# SRIC_Peripherals.net
KiCad netlist of a schematic drawn in Altium Designer
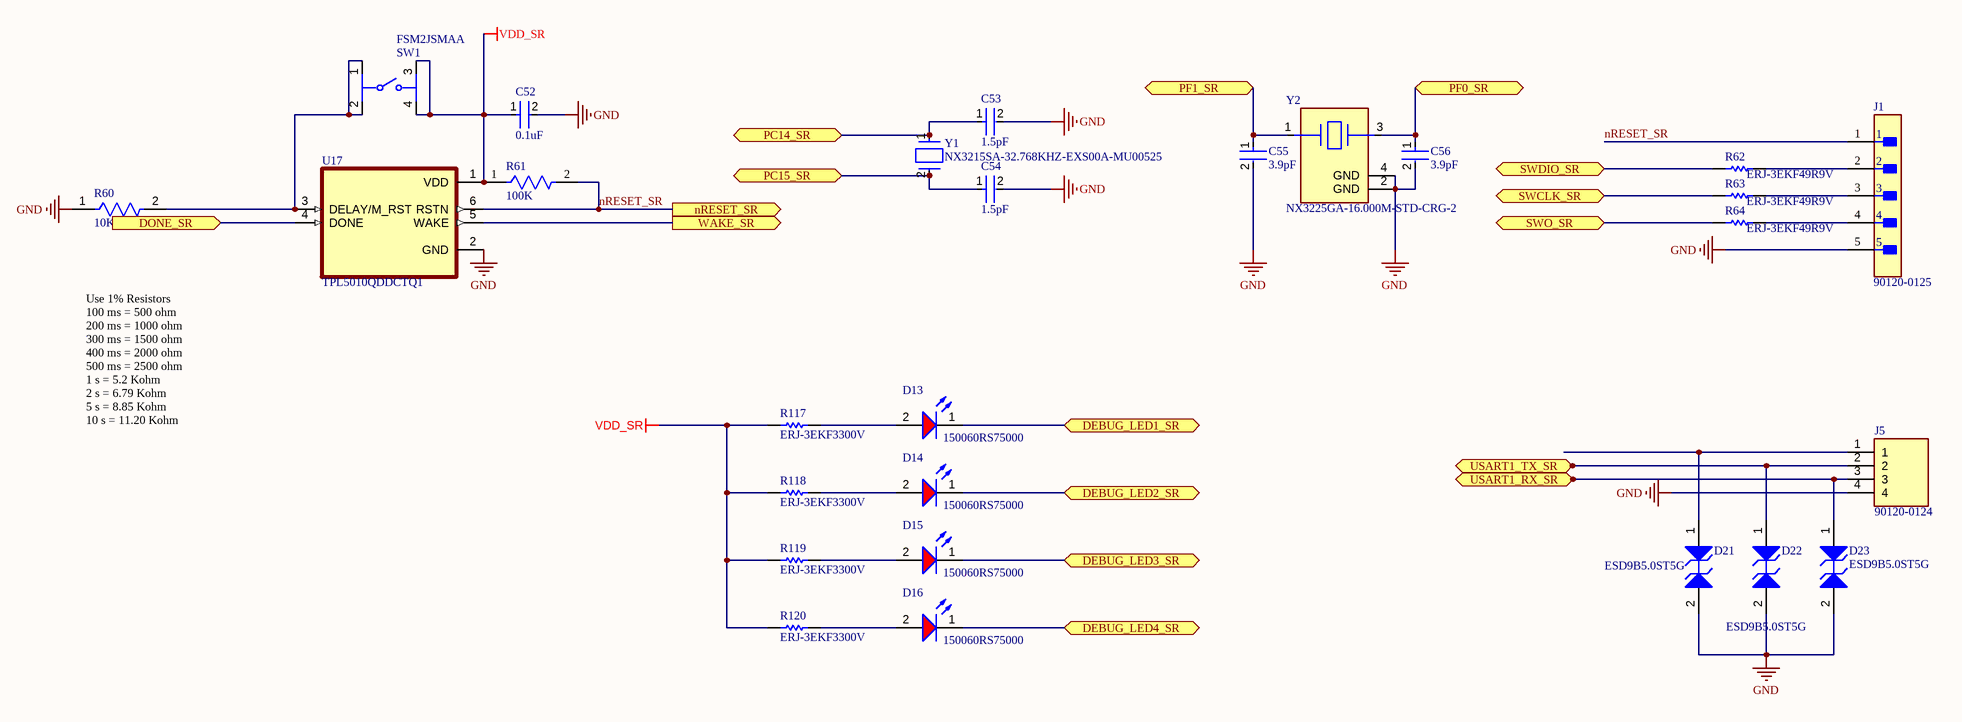
[diagram p0: SRIC_Peripherals.SchDoc]

(export (version "E")
  (design (tool "Eeschema 10.0.6"))
  (components
    (comp (ref "C52")
      (value "0.1uF")
      (footprint "FP-C0603C-CF-MFG")
      (description "CAP CER 0.1UF 50V X7R 0603")
      (fields (field (name "TOLERANCE") "0.1") (field (name "MANUFACTURER") "KEMET"))
      (libsource (lib "Altium Content Vault") (part "b4654b650e69147ec39a6b967a45e02"))
    )
    (comp (ref "C53")
      (value "1.5pF")
      (footprint "FP-C0603C-CF-MFG")
      (description "CAP CER 1.5PF 100V NP0 0603")
      (fields
        (field (name "MANUFACTURER PART NUMBER") "C0603C159C1GACTU")
        (field (name "TOLERANCE") "0.25 pF")
      )
      (libsource (lib "Altium Content Vault") (part "b4654b650e69147ec39a6b967a45e02"))
    )
    (comp (ref "C54")
      (value "1.5pF")
      (footprint "FP-C0603C-CF-MFG")
      (description "CAP CER 1.5PF 100V NP0 0603")
      (fields
        (field (name "MANUFACTURER PART NUMBER") "C0603C159C1GACTU")
        (field (name "TOLERANCE") "0.25 pF")
      )
      (libsource (lib "Altium Content Vault") (part "b4654b650e69147ec39a6b967a45e02"))
    )
    (comp (ref "C55")
      (value "3.9pF")
      (footprint "FP-CBR06C-MFG")
      (description "CAP CER 3.9PF 250V C0G/NP0 0603")
      (fields
        (field (name "OCTOPART") "https://octopart.com/cbr06c399cagac-kemet-20446767")
        (field (name "MANUFACTURER PART NUMBER") "CBR06C399CAGAC")
      )
      (libsource (lib "Altium Content Vault") (part "11868f565c42a9108669ba33697ecf6"))
    )
    (comp (ref "C56")
      (value "3.9pF")
      (footprint "FP-CBR06C-MFG")
      (description "CAP CER 3.9PF 250V C0G/NP0 0603")
      (fields
        (field (name "OCTOPART") "https://octopart.com/cbr06c399cagac-kemet-20446767")
        (field (name "MANUFACTURER PART NUMBER") "CBR06C399CAGAC")
      )
      (libsource (lib "Altium Content Vault") (part "11868f565c42a9108669ba33697ecf6"))
    )
    (comp (ref "D13")
      (value "150060RS75000")
      (footprint "WL-SMCW_0603_150060xx75000")
      (description "LED Low-Power Uni-Color Red 630nm 2V 2-Pin Chip 0603(1608Metric) T/R")
      (libsource (lib "Altium Content Vault") (part "LED_Red_2A-1K"))
    )
    (comp (ref "D14")
      (value "150060RS75000")
      (footprint "WL-SMCW_0603_150060xx75000")
      (description "LED Low-Power Uni-Color Red 630nm 2V 2-Pin Chip 0603(1608Metric) T/R")
      (libsource (lib "Altium Content Vault") (part "LED_Red_2A-1K"))
    )
    (comp (ref "D15")
      (value "150060RS75000")
      (footprint "WL-SMCW_0603_150060xx75000")
      (description "LED Low-Power Uni-Color Red 630nm 2V 2-Pin Chip 0603(1608Metric) T/R")
      (libsource (lib "Altium Content Vault") (part "LED_Red_2A-1K"))
    )
    (comp (ref "D16")
      (value "150060RS75000")
      (footprint "WL-SMCW_0603_150060xx75000")
      (description "LED Low-Power Uni-Color Red 630nm 2V 2-Pin Chip 0603(1608Metric) T/R")
      (libsource (lib "Altium Content Vault") (part "LED_Red_2A-1K"))
    )
    (comp (ref "D21")
      (value "ESD9B5.0ST5G")
      (footprint "ONSC-SOD-923-2-514AB-01_V")
      (fields (field (name "MANUFACTURER") "On Semiconductor"))
      (libsource (lib "Altium Content Vault") (part "ONSC-A1A2-2"))
    )
    (comp (ref "D22")
      (value "ESD9B5.0ST5G")
      (footprint "ONSC-SOD-923-2-514AB-01_V")
      (fields (field (name "MANUFACTURER") "On Semiconductor"))
      (libsource (lib "Altium Content Vault") (part "ONSC-A1A2-2"))
    )
    (comp (ref "D23")
      (value "ESD9B5.0ST5G")
      (footprint "ONSC-SOD-923-2-514AB-01_V")
      (fields (field (name "MANUFACTURER") "On Semiconductor"))
      (libsource (lib "Altium Content Vault") (part "ONSC-A1A2-2"))
    )
    (comp (ref "J1")
      (value "90120-0125")
      (footprint "FP-90120-0125-MFG")
      (description "90120-0125 2.54mm Pitch C-Grid III Header, Single Row, Vertical, 5 Circuits, Tin (Sn) Plating")
      (libsource (lib "Altium Content Vault") (part "bf93c07fd2649a848d0ec8585582aab"))
    )
    (comp (ref "J5")
      (value "90120-0124")
      (footprint "SamacSys:HDRV4W65P0X254_1X4_1016X254X945P")
      (description "Connector")
      (fields (field (name "MOUSER PART NUMBER") "538-90120-0124"))
      (libsource (lib "*") (part "90120-0124"))
    )
    (comp (ref "R60")
      (value "10K")
      (footprint "FP-RK73B1J-MFG")
      (description "RES 10K OHM 5% 1/10W 0603")
      (fields (field (name "TOLERANCE") "5%"))
      (libsource (lib "Altium Content Vault") (part "1029c3af85768c4190bb7ad29bc67b5"))
    )
    (comp (ref "R61")
      (value "100K")
      (footprint "FP-ERA3A-MFG")
      (fields (field (name "TOLERANCE") "0.1%"))
      (libsource (lib "Altium Content Vault") (part "1029c3af85768c4190bb7ad29bc67b5"))
    )
    (comp (ref "R62")
      (value "ERJ-3EKF49R9V")
      (footprint "RESC1608X55X30ML15T15")
      (fields (field (name "MANUFACTURER") "Panasonic"))
      (libsource (lib "Altium Content Vault") (part "RES"))
    )
    (comp (ref "R63")
      (value "ERJ-3EKF49R9V")
      (footprint "RESC1608X55X30ML15T15")
      (fields (field (name "MANUFACTURER") "Panasonic"))
      (libsource (lib "Altium Content Vault") (part "RES"))
    )
    (comp (ref "R64")
      (value "ERJ-3EKF49R9V")
      (footprint "RESC1608X55X30ML15T15")
      (fields (field (name "MANUFACTURER") "Panasonic"))
      (libsource (lib "Altium Content Vault") (part "RES"))
    )
    (comp (ref "R117")
      (value "ERJ-3EKF3300V")
      (footprint "RESC1608X55X30LL15T15")
      (description "Chip Resistor, 330 Ohm, +/- 1%, 0.1 W, -55 to 155 degC, 0603 (1608 Metric), RoHS, Tape and Reel")
      (libsource (lib "Altium Content Vault") (part "RES-2"))
    )
    (comp (ref "R118")
      (value "ERJ-3EKF3300V")
      (footprint "RESC1608X55X30LL15T15")
      (description "Chip Resistor, 330 Ohm, +/- 1%, 0.1 W, -55 to 155 degC, 0603 (1608 Metric), RoHS, Tape and Reel")
      (libsource (lib "Altium Content Vault") (part "RES-2"))
    )
    (comp (ref "R119")
      (value "ERJ-3EKF3300V")
      (footprint "RESC1608X55X30LL15T15")
      (description "Chip Resistor, 330 Ohm, +/- 1%, 0.1 W, -55 to 155 degC, 0603 (1608 Metric), RoHS, Tape and Reel")
      (libsource (lib "Altium Content Vault") (part "RES-2"))
    )
    (comp (ref "R120")
      (value "ERJ-3EKF3300V")
      (footprint "RESC1608X55X30LL15T15")
      (description "Chip Resistor, 330 Ohm, +/- 1%, 0.1 W, -55 to 155 degC, 0603 (1608 Metric), RoHS, Tape and Reel")
      (libsource (lib "Altium Content Vault") (part "RES-2"))
    )
    (comp (ref "SW1")
      (value "FSM2JSMAA")
      (footprint "FP-FSM2JSMAA-MFG")
      (description "SWITCH TACTILE SPST-NO 0.05A 24V")
      (fields
        (field (name "MANUFACTURER") "TE Connectivity")
        (field (name "OCTOPART") "https://octopart.com/fsm2jsmaa-te+connectivity-41720620")
      )
      (libsource (lib "Altium Content Vault") (part "b8895f3f4cefb76e1819d2863dba89b"))
    )
    (comp (ref "U17")
      (value "TPL5010QDDCTQ1")
      (footprint "SOT95P280X110-6N")
      (description "Automotive AEC-Q100, nano-powered system timer with watchdog function")
      (fields (field (name "MF") "Texas Instruments"))
      (libsource (lib "Hitesh Bhoyar") (part "TPL5010QDDCTQ1"))
    )
    (comp (ref "Y1")
      (value "NX3215SA-32.768KHZ-EXS00A-MU00525")
      (footprint "FP-NX3215SA-MFG")
      (description "CRYSTAL 32.7680KHZ 6PF SMD")
      (libsource (lib "Altium Content Vault") (part "c23a69dc6c9e2f18f2079038eb95dd1"))
    )
    (comp (ref "Y2")
      (value "NX3225GA-16.000M-STD-CRG-2")
      (footprint "FP-NX3225GA-MFG")
      (description "CRYSTAL 16.0000MHZ 8PF SMD")
      (libsource (lib "Altium Content Vault") (part "6320effb7d3e443b36bf79d8ebe02e5"))
    )
  )
  (nets
    (net (code "1") (name "/DEBUG_LED1_SR") (class "Default")
      (node (ref "D13") (pin "1") (pinfunction "K_1") (pintype "passive"))
    )
    (net (code "2") (name "/DEBUG_LED2_SR") (class "Default")
      (node (ref "D14") (pin "1") (pinfunction "K_1") (pintype "passive"))
    )
    (net (code "3") (name "/DEBUG_LED3_SR") (class "Default")
      (node (ref "D15") (pin "1") (pinfunction "K_1") (pintype "passive"))
    )
    (net (code "4") (name "/DEBUG_LED4_SR") (class "Default")
      (node (ref "D16") (pin "1") (pinfunction "K_1") (pintype "passive"))
    )
    (net (code "5") (name "/DONE_SR") (class "Default")
      (node (ref "U17") (pin "4") (pinfunction "DONE_4") (pintype "input"))
    )
    (net (code "6") (name "/PC14_SR") (class "Default")
      (node (ref "C53") (pin "1") (pinfunction "1_1") (pintype "passive"))
      (node (ref "Y1") (pin "1") (pinfunction "1_1") (pintype "passive"))
    )
    (net (code "7") (name "/PC15_SR") (class "Default")
      (node (ref "C54") (pin "1") (pinfunction "1_1") (pintype "passive"))
      (node (ref "Y1") (pin "2") (pinfunction "2_2") (pintype "passive"))
    )
    (net (code "8") (name "/PF0_SR") (class "Default")
      (node (ref "C56") (pin "1") (pinfunction "1_1") (pintype "passive"))
      (node (ref "Y2") (pin "3") (pinfunction "3_3") (pintype "passive"))
    )
    (net (code "9") (name "/PF1_SR") (class "Default")
      (node (ref "C55") (pin "1") (pinfunction "1_1") (pintype "passive"))
      (node (ref "Y2") (pin "1") (pinfunction "1_1") (pintype "passive"))
    )
    (net (code "10") (name "/SWCLK_SR") (class "Default")
      (node (ref "R63") (pin "1") (pinfunction "1_1") (pintype "passive"))
    )
    (net (code "11") (name "/SWDIO_SR") (class "Default")
      (node (ref "R62") (pin "1") (pinfunction "1_1") (pintype "passive"))
    )
    (net (code "12") (name "/SWO_SR") (class "Default")
      (node (ref "R64") (pin "1") (pinfunction "1_1") (pintype "passive"))
    )
    (net (code "13") (name "/USART1_RX_SR") (class "Default")
      (node (ref "D23") (pin "1") (pinfunction "A1_1") (pintype "passive"))
      (node (ref "J5") (pin "3") (pinfunction "3_3") (pintype "passive"))
    )
    (net (code "14") (name "/USART1_TX_SR") (class "Default")
      (node (ref "D22") (pin "1") (pinfunction "A1_1") (pintype "passive"))
      (node (ref "J5") (pin "2") (pinfunction "2_2") (pintype "passive"))
    )
    (net (code "15") (name "/WAKE_SR") (class "Default")
      (node (ref "U17") (pin "5") (pinfunction "WAKE_5") (pintype "output"))
    )
    (net (code "16") (name "/nRESET_SR") (class "Default")
      (node (ref "J1") (pin "1") (pinfunction "1_1") (pintype "passive"))
      (node (ref "R61") (pin "2") (pinfunction "2_2") (pintype "passive"))
      (node (ref "U17") (pin "6") (pinfunction "RSTN_6") (pintype "output"))
    )
    (net (code "17") (name "GND") (class "Default")
      (node (ref "C52") (pin "2") (pinfunction "2_2") (pintype "passive"))
      (node (ref "C53") (pin "2") (pinfunction "2_2") (pintype "passive"))
      (node (ref "C54") (pin "2") (pinfunction "2_2") (pintype "passive"))
      (node (ref "C55") (pin "2") (pinfunction "2_2") (pintype "passive"))
      (node (ref "C56") (pin "2") (pinfunction "2_2") (pintype "passive"))
      (node (ref "D21") (pin "2") (pinfunction "A2_2") (pintype "passive"))
      (node (ref "D22") (pin "2") (pinfunction "A2_2") (pintype "passive"))
      (node (ref "D23") (pin "2") (pinfunction "A2_2") (pintype "passive"))
      (node (ref "J1") (pin "5") (pinfunction "5_5") (pintype "passive"))
      (node (ref "J5") (pin "4") (pinfunction "4_4") (pintype "passive"))
      (node (ref "R60") (pin "1") (pinfunction "1_1") (pintype "passive"))
      (node (ref "U17") (pin "2") (pinfunction "GND_2") (pintype "power_in"))
      (node (ref "Y2") (pin "2") (pinfunction "GND_2") (pintype "power_in"))
      (node (ref "Y2") (pin "4") (pinfunction "GND_4") (pintype "power_in"))
    )
    (net (code "18") (name "Net-(D13-A)") (class "Default")
      (node (ref "D13") (pin "2") (pinfunction "A_2") (pintype "passive"))
      (node (ref "R117") (pin "2") (pinfunction "2_2") (pintype "passive"))
    )
    (net (code "19") (name "Net-(D14-A)") (class "Default")
      (node (ref "D14") (pin "2") (pinfunction "A_2") (pintype "passive"))
      (node (ref "R118") (pin "2") (pinfunction "2_2") (pintype "passive"))
    )
    (net (code "20") (name "Net-(D15-A)") (class "Default")
      (node (ref "D15") (pin "2") (pinfunction "A_2") (pintype "passive"))
      (node (ref "R119") (pin "2") (pinfunction "2_2") (pintype "passive"))
    )
    (net (code "21") (name "Net-(D16-A)") (class "Default")
      (node (ref "D16") (pin "2") (pinfunction "A_2") (pintype "passive"))
      (node (ref "R120") (pin "2") (pinfunction "2_2") (pintype "passive"))
    )
    (net (code "22") (name "Net-(D21-A1)") (class "Default")
      (node (ref "D21") (pin "1") (pinfunction "A1_1") (pintype "passive"))
      (node (ref "J5") (pin "1") (pinfunction "1_1") (pintype "passive"))
    )
    (net (code "23") (name "Net-(J1-Pad2)") (class "Default")
      (node (ref "J1") (pin "2") (pinfunction "2_2") (pintype "passive"))
      (node (ref "R62") (pin "2") (pinfunction "2_2") (pintype "passive"))
    )
    (net (code "24") (name "Net-(J1-Pad3)") (class "Default")
      (node (ref "J1") (pin "3") (pinfunction "3_3") (pintype "passive"))
      (node (ref "R63") (pin "2") (pinfunction "2_2") (pintype "passive"))
    )
    (net (code "25") (name "Net-(J1-Pad4)") (class "Default")
      (node (ref "J1") (pin "4") (pinfunction "4_4") (pintype "passive"))
      (node (ref "R64") (pin "2") (pinfunction "2_2") (pintype "passive"))
    )
    (net (code "26") (name "Net-(U17-DELAY{slash}M_RST)") (class "Default")
      (node (ref "R60") (pin "2") (pinfunction "2_2") (pintype "passive"))
      (node (ref "SW1") (pin "1") (pinfunction "1_1") (pintype "passive"))
      (node (ref "SW1") (pin "2") (pinfunction "2_2") (pintype "passive"))
      (node (ref "U17") (pin "3") (pinfunction "DELAY/M_RST_3") (pintype "input"))
    )
    (net (code "27") (name "VDD_SR") (class "Default")
      (node (ref "C52") (pin "1") (pinfunction "1_1") (pintype "passive"))
      (node (ref "R117") (pin "1") (pinfunction "1_1") (pintype "passive"))
      (node (ref "R118") (pin "1") (pinfunction "1_1") (pintype "passive"))
      (node (ref "R119") (pin "1") (pinfunction "1_1") (pintype "passive"))
      (node (ref "R120") (pin "1") (pinfunction "1_1") (pintype "passive"))
      (node (ref "R61") (pin "1") (pinfunction "1_1") (pintype "passive"))
      (node (ref "SW1") (pin "3") (pinfunction "3_3") (pintype "passive"))
      (node (ref "SW1") (pin "4") (pinfunction "4_4") (pintype "passive"))
      (node (ref "U17") (pin "1") (pinfunction "VDD_1") (pintype "power_in"))
    )
  )
)
